# eLite_Clock_-_Alpha_Board.net
KiCad netlist of a schematic drawn in EAGLE
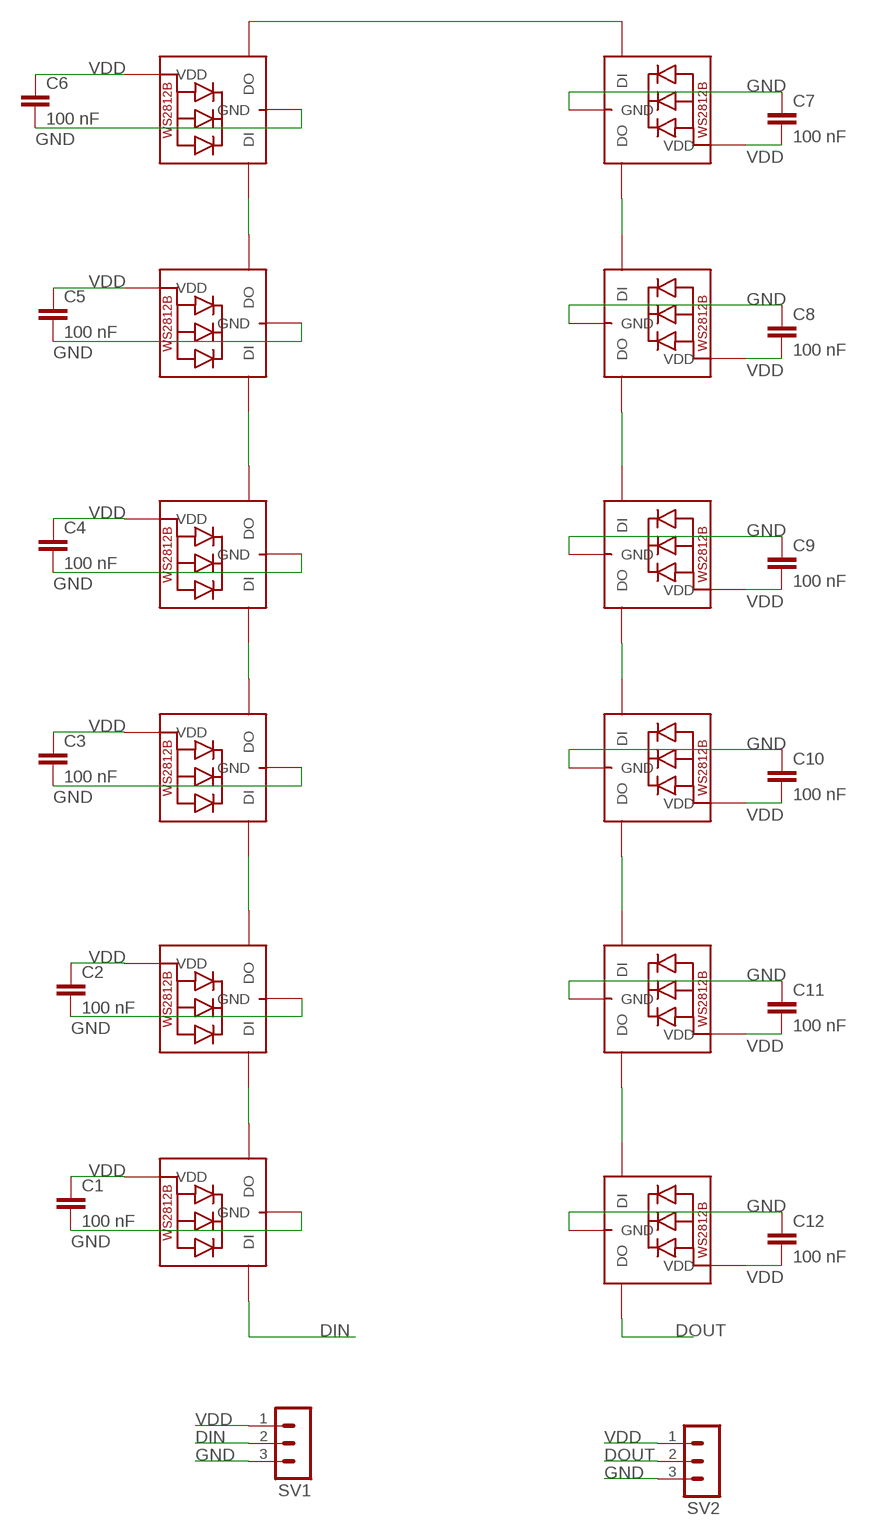
[diagram p0: schematic, sheet 1]

(export (version "E")
  (design (tool "Eeschema 10.0.6"))
  (components
    (comp (ref "C1")
      (value "100 nF")
      (footprint "eagle-import:C025-025X050")
      (libsource (lib "eagle-import") (part "C-EU025-025X050"))
    )
    (comp (ref "C2")
      (value "100 nF")
      (footprint "eagle-import:C025-025X050")
      (libsource (lib "eagle-import") (part "C-EU025-025X050"))
    )
    (comp (ref "C3")
      (value "100 nF")
      (footprint "eagle-import:C025-025X050")
      (libsource (lib "eagle-import") (part "C-EU025-025X050"))
    )
    (comp (ref "C4")
      (value "100 nF")
      (footprint "eagle-import:C025-025X050")
      (libsource (lib "eagle-import") (part "C-EU025-025X050"))
    )
    (comp (ref "C5")
      (value "100 nF")
      (footprint "eagle-import:C025-025X050")
      (libsource (lib "eagle-import") (part "C-EU025-025X050"))
    )
    (comp (ref "C6")
      (value "100 nF")
      (footprint "eagle-import:C025-025X050")
      (libsource (lib "eagle-import") (part "C-EU025-025X050"))
    )
    (comp (ref "C7")
      (value "100 nF")
      (footprint "eagle-import:C025-025X050")
      (libsource (lib "eagle-import") (part "C-EU025-025X050"))
    )
    (comp (ref "C8")
      (value "100 nF")
      (footprint "eagle-import:C025-025X050")
      (libsource (lib "eagle-import") (part "C-EU025-025X050"))
    )
    (comp (ref "C9")
      (value "100 nF")
      (footprint "eagle-import:C025-025X050")
      (libsource (lib "eagle-import") (part "C-EU025-025X050"))
    )
    (comp (ref "C10")
      (value "100 nF")
      (footprint "eagle-import:C025-025X050")
      (libsource (lib "eagle-import") (part "C-EU025-025X050"))
    )
    (comp (ref "C11")
      (value "100 nF")
      (footprint "eagle-import:C025-025X050")
      (libsource (lib "eagle-import") (part "C-EU025-025X050"))
    )
    (comp (ref "C12")
      (value "100 nF")
      (footprint "eagle-import:C025-025X050")
      (libsource (lib "eagle-import") (part "C-EU025-025X050"))
    )
    (comp (ref "LED1")
      (value "WS2812B_5050W")
      (footprint "eagle-import:WS2812B-WIDE")
      (libsource (lib "eagle-import") (part "WS2812B_5050W"))
    )
    (comp (ref "LED2")
      (value "WS2812B_5050W")
      (footprint "eagle-import:WS2812B-WIDE")
      (libsource (lib "eagle-import") (part "WS2812B_5050W"))
    )
    (comp (ref "LED3")
      (value "WS2812B_5050W")
      (footprint "eagle-import:WS2812B-WIDE")
      (libsource (lib "eagle-import") (part "WS2812B_5050W"))
    )
    (comp (ref "LED4")
      (value "WS2812B_5050W")
      (footprint "eagle-import:WS2812B-WIDE")
      (libsource (lib "eagle-import") (part "WS2812B_5050W"))
    )
    (comp (ref "LED5")
      (value "WS2812B_5050W")
      (footprint "eagle-import:WS2812B-WIDE")
      (libsource (lib "eagle-import") (part "WS2812B_5050W"))
    )
    (comp (ref "LED6")
      (value "WS2812B_5050W")
      (footprint "eagle-import:WS2812B-WIDE")
      (libsource (lib "eagle-import") (part "WS2812B_5050W"))
    )
    (comp (ref "LED7")
      (value "WS2812B_5050W")
      (footprint "eagle-import:WS2812B-WIDE")
      (libsource (lib "eagle-import") (part "WS2812B_5050W"))
    )
    (comp (ref "LED8")
      (value "WS2812B_5050W")
      (footprint "eagle-import:WS2812B-WIDE")
      (libsource (lib "eagle-import") (part "WS2812B_5050W"))
    )
    (comp (ref "LED9")
      (value "WS2812B_5050W")
      (footprint "eagle-import:WS2812B-WIDE")
      (libsource (lib "eagle-import") (part "WS2812B_5050W"))
    )
    (comp (ref "LED10")
      (value "WS2812B_5050W")
      (footprint "eagle-import:WS2812B-WIDE")
      (libsource (lib "eagle-import") (part "WS2812B_5050W"))
    )
    (comp (ref "LED11")
      (value "WS2812B_5050W")
      (footprint "eagle-import:WS2812B-WIDE")
      (libsource (lib "eagle-import") (part "WS2812B_5050W"))
    )
    (comp (ref "LED12")
      (value "WS2812B_5050W")
      (footprint "eagle-import:WS2812B-WIDE")
      (libsource (lib "eagle-import") (part "WS2812B_5050W"))
    )
    (comp (ref "SV1")
      (value "MA03-1")
      (footprint "eagle-import:MA03-1")
      (libsource (lib "eagle-import") (part "MA03-1"))
    )
    (comp (ref "SV2")
      (value "MA03-1")
      (footprint "eagle-import:MA03-1")
      (libsource (lib "eagle-import") (part "MA03-1"))
    )
  )
  (nets
    (net (code "1") (name "/DIN") (class "Default")
      (node (ref "LED1") (pin "4-DIN") (pinfunction "DI_4-DIN") (pintype "input"))
      (node (ref "SV1") (pin "2") (pinfunction "2_2") (pintype "passive"))
    )
    (net (code "2") (name "/DOUT") (class "Default")
      (node (ref "LED12") (pin "2-DOUT") (pinfunction "DO_2-DOUT") (pintype "output"))
      (node (ref "SV2") (pin "2") (pinfunction "2_2") (pintype "passive"))
    )
    (net (code "3") (name "/GND") (class "Default")
      (node (ref "C1") (pin "2") (pinfunction "2_2") (pintype "passive"))
      (node (ref "C10") (pin "1") (pinfunction "1_1") (pintype "passive"))
      (node (ref "C11") (pin "1") (pinfunction "1_1") (pintype "passive"))
      (node (ref "C12") (pin "1") (pinfunction "1_1") (pintype "passive"))
      (node (ref "C2") (pin "2") (pinfunction "2_2") (pintype "passive"))
      (node (ref "C3") (pin "2") (pinfunction "2_2") (pintype "passive"))
      (node (ref "C4") (pin "2") (pinfunction "2_2") (pintype "passive"))
      (node (ref "C5") (pin "2") (pinfunction "2_2") (pintype "passive"))
      (node (ref "C6") (pin "2") (pinfunction "2_2") (pintype "passive"))
      (node (ref "C7") (pin "1") (pinfunction "1_1") (pintype "passive"))
      (node (ref "C8") (pin "1") (pinfunction "1_1") (pintype "passive"))
      (node (ref "C9") (pin "1") (pinfunction "1_1") (pintype "passive"))
      (node (ref "LED1") (pin "3-GND") (pinfunction "GND_3-GND") (pintype "power_in"))
      (node (ref "LED10") (pin "3-GND") (pinfunction "GND_3-GND") (pintype "power_in"))
      (node (ref "LED11") (pin "3-GND") (pinfunction "GND_3-GND") (pintype "power_in"))
      (node (ref "LED12") (pin "3-GND") (pinfunction "GND_3-GND") (pintype "power_in"))
      (node (ref "LED2") (pin "3-GND") (pinfunction "GND_3-GND") (pintype "power_in"))
      (node (ref "LED3") (pin "3-GND") (pinfunction "GND_3-GND") (pintype "power_in"))
      (node (ref "LED4") (pin "3-GND") (pinfunction "GND_3-GND") (pintype "power_in"))
      (node (ref "LED5") (pin "3-GND") (pinfunction "GND_3-GND") (pintype "power_in"))
      (node (ref "LED6") (pin "3-GND") (pinfunction "GND_3-GND") (pintype "power_in"))
      (node (ref "LED7") (pin "3-GND") (pinfunction "GND_3-GND") (pintype "power_in"))
      (node (ref "LED8") (pin "3-GND") (pinfunction "GND_3-GND") (pintype "power_in"))
      (node (ref "LED9") (pin "3-GND") (pinfunction "GND_3-GND") (pintype "power_in"))
      (node (ref "SV1") (pin "3") (pinfunction "3_3") (pintype "passive"))
      (node (ref "SV2") (pin "3") (pinfunction "3_3") (pintype "passive"))
    )
    (net (code "4") (name "/VDD") (class "Default")
      (node (ref "C1") (pin "1") (pinfunction "1_1") (pintype "passive"))
      (node (ref "C10") (pin "2") (pinfunction "2_2") (pintype "passive"))
      (node (ref "C11") (pin "2") (pinfunction "2_2") (pintype "passive"))
      (node (ref "C12") (pin "2") (pinfunction "2_2") (pintype "passive"))
      (node (ref "C2") (pin "1") (pinfunction "1_1") (pintype "passive"))
      (node (ref "C3") (pin "1") (pinfunction "1_1") (pintype "passive"))
      (node (ref "C4") (pin "1") (pinfunction "1_1") (pintype "passive"))
      (node (ref "C5") (pin "1") (pinfunction "1_1") (pintype "passive"))
      (node (ref "C6") (pin "1") (pinfunction "1_1") (pintype "passive"))
      (node (ref "C7") (pin "2") (pinfunction "2_2") (pintype "passive"))
      (node (ref "C8") (pin "2") (pinfunction "2_2") (pintype "passive"))
      (node (ref "C9") (pin "2") (pinfunction "2_2") (pintype "passive"))
      (node (ref "LED1") (pin "1-VDD") (pinfunction "VDD_1-VDD") (pintype "power_in"))
      (node (ref "LED10") (pin "1-VDD") (pinfunction "VDD_1-VDD") (pintype "power_in"))
      (node (ref "LED11") (pin "1-VDD") (pinfunction "VDD_1-VDD") (pintype "power_in"))
      (node (ref "LED12") (pin "1-VDD") (pinfunction "VDD_1-VDD") (pintype "power_in"))
      (node (ref "LED2") (pin "1-VDD") (pinfunction "VDD_1-VDD") (pintype "power_in"))
      (node (ref "LED3") (pin "1-VDD") (pinfunction "VDD_1-VDD") (pintype "power_in"))
      (node (ref "LED4") (pin "1-VDD") (pinfunction "VDD_1-VDD") (pintype "power_in"))
      (node (ref "LED5") (pin "1-VDD") (pinfunction "VDD_1-VDD") (pintype "power_in"))
      (node (ref "LED6") (pin "1-VDD") (pinfunction "VDD_1-VDD") (pintype "power_in"))
      (node (ref "LED7") (pin "1-VDD") (pinfunction "VDD_1-VDD") (pintype "power_in"))
      (node (ref "LED8") (pin "1-VDD") (pinfunction "VDD_1-VDD") (pintype "power_in"))
      (node (ref "LED9") (pin "1-VDD") (pinfunction "VDD_1-VDD") (pintype "power_in"))
      (node (ref "SV1") (pin "1") (pinfunction "1_1") (pintype "passive"))
      (node (ref "SV2") (pin "1") (pinfunction "1_1") (pintype "passive"))
    )
    (net (code "5") (name "Net-(LED1-DO)") (class "Default")
      (node (ref "LED1") (pin "2-DOUT") (pinfunction "DO_2-DOUT") (pintype "output"))
      (node (ref "LED2") (pin "4-DIN") (pinfunction "DI_4-DIN") (pintype "input"))
    )
    (net (code "6") (name "Net-(LED2-DO)") (class "Default")
      (node (ref "LED2") (pin "2-DOUT") (pinfunction "DO_2-DOUT") (pintype "output"))
      (node (ref "LED3") (pin "4-DIN") (pinfunction "DI_4-DIN") (pintype "input"))
    )
    (net (code "7") (name "Net-(LED3-DO)") (class "Default")
      (node (ref "LED3") (pin "2-DOUT") (pinfunction "DO_2-DOUT") (pintype "output"))
      (node (ref "LED4") (pin "4-DIN") (pinfunction "DI_4-DIN") (pintype "input"))
    )
    (net (code "8") (name "Net-(LED4-DO)") (class "Default")
      (node (ref "LED4") (pin "2-DOUT") (pinfunction "DO_2-DOUT") (pintype "output"))
      (node (ref "LED5") (pin "4-DIN") (pinfunction "DI_4-DIN") (pintype "input"))
    )
    (net (code "9") (name "Net-(LED5-DO)") (class "Default")
      (node (ref "LED5") (pin "2-DOUT") (pinfunction "DO_2-DOUT") (pintype "output"))
      (node (ref "LED6") (pin "4-DIN") (pinfunction "DI_4-DIN") (pintype "input"))
    )
    (net (code "10") (name "Net-(LED6-DO)") (class "Default")
      (node (ref "LED6") (pin "2-DOUT") (pinfunction "DO_2-DOUT") (pintype "output"))
      (node (ref "LED7") (pin "4-DIN") (pinfunction "DI_4-DIN") (pintype "input"))
    )
    (net (code "11") (name "Net-(LED7-DO)") (class "Default")
      (node (ref "LED7") (pin "2-DOUT") (pinfunction "DO_2-DOUT") (pintype "output"))
      (node (ref "LED8") (pin "4-DIN") (pinfunction "DI_4-DIN") (pintype "input"))
    )
    (net (code "12") (name "Net-(LED8-DO)") (class "Default")
      (node (ref "LED8") (pin "2-DOUT") (pinfunction "DO_2-DOUT") (pintype "output"))
      (node (ref "LED9") (pin "4-DIN") (pinfunction "DI_4-DIN") (pintype "input"))
    )
    (net (code "13") (name "Net-(LED10-DI)") (class "Default")
      (node (ref "LED10") (pin "4-DIN") (pinfunction "DI_4-DIN") (pintype "input"))
      (node (ref "LED9") (pin "2-DOUT") (pinfunction "DO_2-DOUT") (pintype "output"))
    )
    (net (code "14") (name "Net-(LED10-DO)") (class "Default")
      (node (ref "LED10") (pin "2-DOUT") (pinfunction "DO_2-DOUT") (pintype "output"))
      (node (ref "LED11") (pin "4-DIN") (pinfunction "DI_4-DIN") (pintype "input"))
    )
    (net (code "15") (name "Net-(LED11-DO)") (class "Default")
      (node (ref "LED11") (pin "2-DOUT") (pinfunction "DO_2-DOUT") (pintype "output"))
      (node (ref "LED12") (pin "4-DIN") (pinfunction "DI_4-DIN") (pintype "input"))
    )
  )
)
